# power-v3v8.net
KiCad netlist of a schematic drawn in Altium Designer
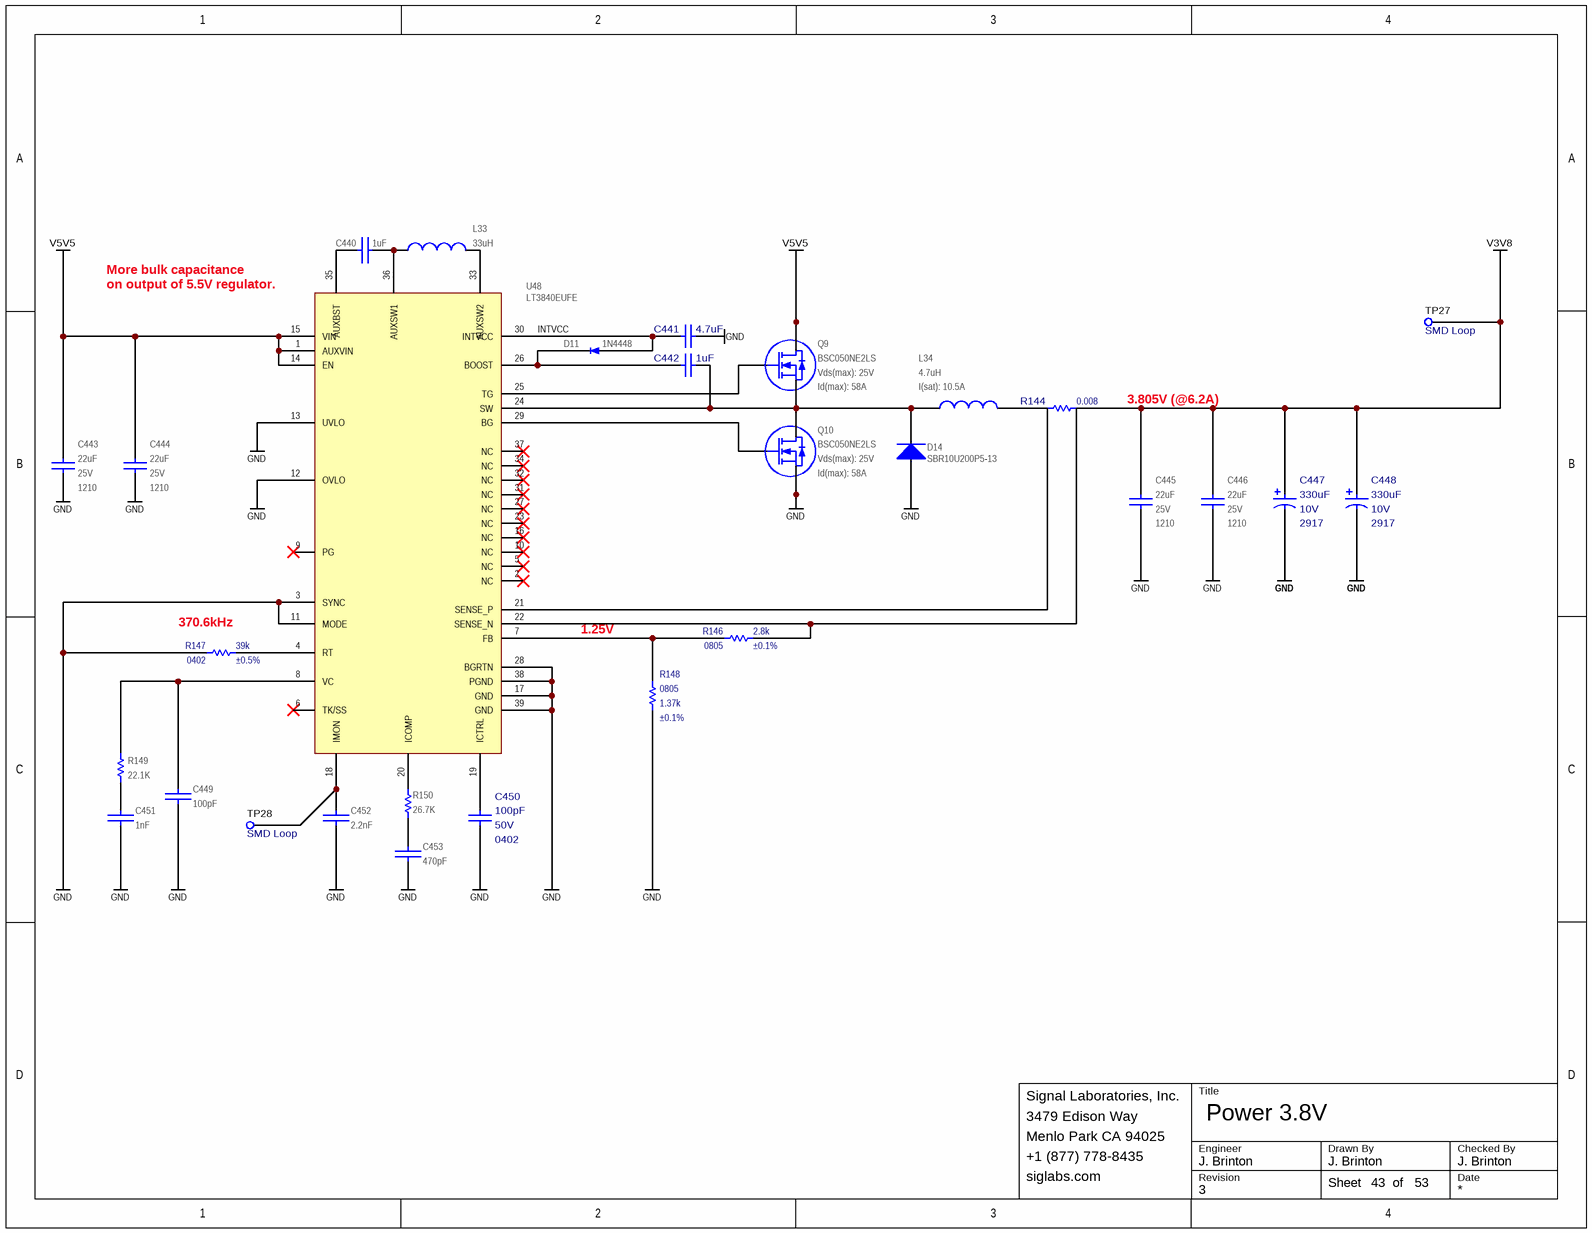
[diagram p0: power-v3v8.SchDoc]

(export (version "E")
  (design (tool "Eeschema 10.0.6"))
  (components
    (comp (ref "C440")
      (value "1uF")
      (footprint "CAPC100X50X55L25N")
      (description "Ceramic Capacitor 1uF ±10% 10V X5R 0402")
      (fields (field (name "MANUFACTURER") "Murata") (field (name "TOLERANCE") "±10%"))
      (libsource (lib "*") (part "CAP"))
    )
    (comp (ref "C441")
      (value "4.7uF")
      (footprint "CAPC160X80X90L20N")
      (description "Ceramic Capacitor 4.7uF ±10% 25V X5R 0603")
      (fields (field (name "MANUFACTURER") "Samsung") (field (name "TOLERANCE") "±10%"))
      (libsource (lib "capacitors") (part "CAP"))
    )
    (comp (ref "C442")
      (value "1uF")
      (footprint "CAPC100X50X55L25N")
      (description "Ceramic Capacitor 1uF ±10% 10V X5R 0402")
      (fields (field (name "MANUFACTURER") "Murata") (field (name "TOLERANCE") "±10%"))
      (libsource (lib "capacitors") (part "CAP"))
    )
    (comp (ref "C443")
      (value "22uF")
      (footprint "CAPC320X250X270L50N")
      (description "Ceramic Capacitor 22uF ±10% 25V X7R 1210")
      (fields
        (field (name "MANUFACTURER") "Murata")
        (field (name "TOLERANCE") "±10%")
        (field (name "VOLTAGE") "25V")
        (field (name "PACKAGE") "1210")
      )
      (libsource (lib "generic") (part "CAP"))
    )
    (comp (ref "C444")
      (value "22uF")
      (footprint "CAPC320X250X270L50N")
      (description "Ceramic Capacitor 22uF ±10% 25V X7R 1210")
      (fields
        (field (name "MANUFACTURER") "Murata")
        (field (name "TOLERANCE") "±10%")
        (field (name "VOLTAGE") "25V")
        (field (name "PACKAGE") "1210")
      )
      (libsource (lib "generic") (part "CAP"))
    )
    (comp (ref "C445")
      (value "22uF")
      (footprint "CAPC320X250X270L50N")
      (description "Ceramic Capacitor 22uF ±10% 25V X7R 1210")
      (fields
        (field (name "MANUFACTURER") "Murata")
        (field (name "TOLERANCE") "±10%")
        (field (name "VOLTAGE") "25V")
        (field (name "PACKAGE") "1210")
      )
      (libsource (lib "generic") (part "CAP"))
    )
    (comp (ref "C446")
      (value "22uF")
      (footprint "CAPC320X250X270L50N")
      (description "Ceramic Capacitor 22uF ±10% 25V X7R 1210")
      (fields
        (field (name "MANUFACTURER") "Murata")
        (field (name "TOLERANCE") "±10%")
        (field (name "VOLTAGE") "25V")
        (field (name "PACKAGE") "1210")
      )
      (libsource (lib "generic") (part "CAP"))
    )
    (comp (ref "C447")
      (value "330uF")
      (footprint "CAPPM730X435X310L135X240N")
      (description "Tantalum Capacitor 330uF ±10% 10V 2917")
      (fields
        (field (name "MANUFACTURER") "AVX")
        (field (name "TOLERANCE") "±10%")
        (field (name "PACKAGE") "2917")
        (field (name "VOLTAGE") "10V")
      )
      (libsource (lib "avx") (part "CAP_POL"))
    )
    (comp (ref "C448")
      (value "330uF")
      (footprint "CAPPM730X435X310L135X240N")
      (description "Tantalum Capacitor 330uF ±10% 10V 2917")
      (fields
        (field (name "MANUFACTURER") "AVX")
        (field (name "TOLERANCE") "±10%")
        (field (name "PACKAGE") "2917")
        (field (name "VOLTAGE") "10V")
      )
      (libsource (lib "avx") (part "CAP_POL"))
    )
    (comp (ref "C449")
      (value "100pF")
      (footprint "CAPC100X50X55L25N")
      (description "Ceramic Capacitor 100pF ±5% 50V NP0 0402")
      (fields (field (name "MANUFACTURER") "Murata") (field (name "VOLTAGE") "50V"))
      (libsource (lib "*") (part "CAP"))
    )
    (comp (ref "C450")
      (value "100pF")
      (footprint "generic:CAPC100X50X55L25N")
      (description "Ceramic Capacitor 100pF ±10% 50V C0G 0402")
      (fields
        (field (name "MANUFACTURER") "Vishay")
        (field (name "TOLERANCE") "±10%")
        (field (name "PACKAGE") "0402")
        (field (name "VOLTAGE") "50V")
      )
      (libsource (lib "capacitors") (part "CAP"))
    )
    (comp (ref "C451")
      (value "1nF")
      (footprint "CAPC100X50X55L25N")
      (description "Ceramic Capacitor 1nF ±5% 50V NP0 0402")
      (fields (field (name "MANUFACTURER") "Murata") (field (name "VOLTAGE") "50V"))
      (libsource (lib "*") (part "CAP"))
    )
    (comp (ref "C452")
      (value "2.2nF")
      (footprint "CAPC100X50X55L25N")
      (description "Ceramic Capacitor 2.2nF ±5% 25V NP0 0402")
      (fields (field (name "MANUFACTURER") "Kemet") (field (name "TOLERANCE") "±5%"))
      (libsource (lib "*") (part "CAP"))
    )
    (comp (ref "C453")
      (value "470pF")
      (footprint "CAPC100X50X55L25N")
      (description "Ceramic Capacitor 470pF ±5% 50V X7R 0402")
      (fields (field (name "MANUFACTURER") "Murata") (field (name "VOLTAGE") "50V"))
      (libsource (lib "*") (part "CAP"))
    )
    (comp (ref "D11")
      (value "1N4448HWS-7-F")
      (footprint "diodes_inc:SOD323")
      (description "Schottky Diode 80V 250mA SOD323")
      (fields (field (name "MANUFACTURER") "Diodes Inc") (field (name "ALTERNATIVE P/N") "1N4448"))
      (libsource (lib "diodes_inc") (part "1N4448HWS-7-F"))
    )
    (comp (ref "D14")
      (value "SBR10U200P5-13")
      (footprint "DIODES_POWERDI5")
      (description "Schottky Diode 200V 10A SMD")
      (fields (field (name "MANUFACTURER") "Diodes Inc"))
      (libsource (lib "diodes_inc") (part "PDS5100H"))
    )
    (comp (ref "L33")
      (value "33uH")
      (footprint "coilcraft:ME3220")
      (description "Inductor 33uH ±10% 500mA SMD")
      (fields (field (name "MANUFACTURER") "Coilcraft") (field (name "TOLERANCE") "±10%"))
      (libsource (lib "CamBoard_Pico_70.19K") (part "COIL"))
    )
    (comp (ref "L34")
      (value "4.7uH")
      (footprint "coilcraft:XAL6060")
      (description "Inductor 4.7uH,10.5A(sat), SMD")
      (fields
        (field (name "MANUFACTURER") "Coilcraft")
        (field (name "I(SAT)") "10.5A")
        (field (name "Comment") "XAL6060-472ME")
      )
      (libsource (lib "CamBoard_Pico_70.19K") (part "COIL"))
    )
    (comp (ref "Q9")
      (value "BSC050NE2LS")
      (footprint "TDSON-8")
      (description "MOSFET N-Channel Enhancement Mode")
      (fields
        (field (name "MANUFACTURER") "Infineon")
        (field (name "VDS(MAX)") "25V")
        (field (name "ID(MAX)") "58A")
      )
      (libsource (lib "infinion") (part "BSC190N15NS3"))
    )
    (comp (ref "Q10")
      (value "BSC050NE2LS")
      (footprint "TDSON-8")
      (description "MOSFET N-Channel Enhancement Mode")
      (fields
        (field (name "MANUFACTURER") "Infineon")
        (field (name "VDS(MAX)") "25V")
        (field (name "ID(MAX)") "58A")
      )
      (libsource (lib "infinion") (part "BSC190N15NS3"))
    )
    (comp (ref "R144")
      (value "0.008")
      (footprint "susumu:KRL3216T4")
      (description "Current Sense Resistor 8 mOhms +/-1% SMD 4-Terminal")
      (fields (field (name "TOLERANCE") "±1%") (field (name "MANUFACTURER") "Susumu"))
      (libsource (lib "susumu") (part "KRL3216T4A-M-R009-F"))
    )
    (comp (ref "R146")
      (value "2.8k")
      (footprint "RESC2012X70N")
      (description "Thin Film Resistor 2.8k +/-0.1% SMD 0805")
      (fields
        (field (name "TOLERANCE") "±0.1%")
        (field (name "MANUFACTURER") "Yageo")
        (field (name "PACKAGE") "0805")
        (field (name "Comment") "RT0805BRD072K8L")
      )
      (libsource (lib "generic") (part "RES"))
    )
    (comp (ref "R147")
      (value "39k")
      (footprint "RESC1005X40N")
      (description "Thin Film Resistor 39k +/-0.5% SMD 0402")
      (fields
        (field (name "TOLERANCE") "±0.5%")
        (field (name "MANUFACTURER") "Susumu")
        (field (name "PACKAGE") "0402")
        (field (name "Comment") "RR0510P-393-D")
      )
      (libsource (lib "generic") (part "RES"))
    )
    (comp (ref "R148")
      (value "1.37k")
      (footprint "RESC2012X70N")
      (description "Thin Film Resistor 1.37k +/-0.1% SMD 0805")
      (fields
        (field (name "TOLERANCE") "±0.1%")
        (field (name "MANUFACTURER") "Yageo")
        (field (name "PACKAGE") "0805")
        (field (name "Comment") "RT0805BRD071K37L")
      )
      (libsource (lib "generic") (part "RES"))
    )
    (comp (ref "R149")
      (value "22.1K")
      (footprint "generic:RESC1005X40N")
      (description "Thick Film Resistor 22.1k ±1% 0402")
      (fields (field (name "MANUFACTURER") "Panasonic") (field (name "TOLERANCE") "±1%"))
      (libsource (lib "Graviton") (part "RES 0402"))
    )
    (comp (ref "R150")
      (value "26.7K")
      (footprint "generic:RESC1005X40N")
      (description "Thick Film Resistor 26.7k ±1% 0402")
      (fields (field (name "MANUFACTURER") "Panasonic") (field (name "TOLERANCE") "±1%"))
      (libsource (lib "Graviton") (part "RES 0402"))
    )
    (comp (ref "TP27")
      (value "5015")
      (footprint "keystone:5015")
      (description "Test Point SMD")
      (fields (field (name "MANUFACTURER") "Keystone") (field (name "NOTES") "SMD Loop"))
      (libsource (lib "generic") (part "TEST_POINT_SMD_50"))
    )
    (comp (ref "TP28")
      (value "5015")
      (footprint "keystone:5015")
      (description "Test Point SMD")
      (fields (field (name "MANUFACTURER") "Keystone") (field (name "NOTES") "SMD Loop"))
      (libsource (lib "generic") (part "TEST_POINT_SMD_50"))
    )
    (comp (ref "U48")
      (value "LT3840EUFE")
      (footprint "linear:QFN39P40_600X400X80L40X20T465X265N")
      (description "Synchronous Regulator Controller")
      (fields (field (name "MANUFACTURER") "Linear Technology"))
      (libsource (lib "linear") (part "LT3840EUFE"))
    )
  )
  (nets
    (net (code "1") (name "/INTVCC") (class "Default")
      (node (ref "C441") (pin "1") (pinfunction "1_1") (pintype "passive"))
      (node (ref "D11") (pin "A") (pinfunction "A_A") (pintype "passive"))
      (node (ref "U48") (pin "30") (pinfunction "INTVCC_30") (pintype "passive"))
    )
    (net (code "2") (name "GND") (class "Default")
      (node (ref "C441") (pin "2") (pinfunction "2_2") (pintype "passive"))
      (node (ref "C443") (pin "1") (pinfunction "1_1") (pintype "passive"))
      (node (ref "C444") (pin "1") (pinfunction "1_1") (pintype "passive"))
      (node (ref "C445") (pin "1") (pinfunction "1_1") (pintype "passive"))
      (node (ref "C446") (pin "1") (pinfunction "1_1") (pintype "passive"))
      (node (ref "C447") (pin "2") (pinfunction "2_2") (pintype "passive"))
      (node (ref "C448") (pin "2") (pinfunction "2_2") (pintype "passive"))
      (node (ref "C449") (pin "1") (pinfunction "1_1") (pintype "passive"))
      (node (ref "C450") (pin "2") (pinfunction "2_2") (pintype "passive"))
      (node (ref "C451") (pin "2") (pinfunction "2_2") (pintype "passive"))
      (node (ref "C452") (pin "2") (pinfunction "2_2") (pintype "passive"))
      (node (ref "C453") (pin "1") (pinfunction "1_1") (pintype "passive"))
      (node (ref "D14") (pin "A") (pinfunction "A_A") (pintype "power_in"))
      (node (ref "Q10") (pin "1") (pinfunction "S_1") (pintype "passive"))
      (node (ref "Q10") (pin "2") (pinfunction "S_2") (pintype "passive"))
      (node (ref "Q10") (pin "3") (pinfunction "S_3") (pintype "passive"))
      (node (ref "R147") (pin "2") (pinfunction "2_2") (pintype "passive"))
      (node (ref "R148") (pin "1") (pinfunction "1_1") (pintype "passive"))
      (node (ref "U48") (pin "11") (pinfunction "MODE_11") (pintype "passive"))
      (node (ref "U48") (pin "12") (pinfunction "OVLO_12") (pintype "passive"))
      (node (ref "U48") (pin "13") (pinfunction "UVLO_13") (pintype "passive"))
      (node (ref "U48") (pin "17") (pinfunction "GND_17") (pintype "passive"))
      (node (ref "U48") (pin "28") (pinfunction "BGRTN_28") (pintype "passive"))
      (node (ref "U48") (pin "3") (pinfunction "SYNC_3") (pintype "passive"))
      (node (ref "U48") (pin "38") (pinfunction "PGND_38") (pintype "passive"))
      (node (ref "U48") (pin "39") (pinfunction "GND_39") (pintype "passive"))
    )
    (net (code "3") (name "Net-(C451-Pad1)") (class "Default")
      (node (ref "C451") (pin "1") (pinfunction "1_1") (pintype "passive"))
      (node (ref "R149") (pin "1") (pinfunction "1_1") (pintype "passive"))
    )
    (net (code "4") (name "Net-(C453-Pad2)") (class "Default")
      (node (ref "C453") (pin "2") (pinfunction "2_2") (pintype "passive"))
      (node (ref "R150") (pin "2") (pinfunction "2_2") (pintype "passive"))
    )
    (net (code "5") (name "Net-(L34-Pad2)") (class "Default")
      (node (ref "L34") (pin "2") (pinfunction "2_2") (pintype "passive"))
      (node (ref "R144") (pin "2") (pinfunction "2_2") (pintype "passive"))
    )
    (net (code "6") (name "Net-(Q9-G)") (class "Default")
      (node (ref "Q9") (pin "4") (pinfunction "G_4") (pintype "passive"))
      (node (ref "U48") (pin "25") (pinfunction "TG_25") (pintype "passive"))
    )
    (net (code "7") (name "Net-(Q10-G)") (class "Default")
      (node (ref "Q10") (pin "4") (pinfunction "G_4") (pintype "passive"))
      (node (ref "U48") (pin "29") (pinfunction "BG_29") (pintype "passive"))
    )
    (net (code "8") (name "Net-(U48-AUXBST)") (class "Default")
      (node (ref "C440") (pin "2") (pinfunction "2_2") (pintype "passive"))
      (node (ref "U48") (pin "35") (pinfunction "AUXBST_35") (pintype "passive"))
    )
    (net (code "9") (name "Net-(U48-AUXSW1)") (class "Default")
      (node (ref "C440") (pin "1") (pinfunction "1_1") (pintype "passive"))
      (node (ref "L33") (pin "1") (pinfunction "1_1") (pintype "passive"))
      (node (ref "U48") (pin "36") (pinfunction "AUXSW1_36") (pintype "passive"))
    )
    (net (code "10") (name "Net-(U48-AUXSW2)") (class "Default")
      (node (ref "L33") (pin "2") (pinfunction "2_2") (pintype "passive"))
      (node (ref "U48") (pin "33") (pinfunction "AUXSW2_33") (pintype "passive"))
    )
    (net (code "11") (name "Net-(U48-BOOST)") (class "Default")
      (node (ref "C442") (pin "1") (pinfunction "1_1") (pintype "passive"))
      (node (ref "D11") (pin "K") (pinfunction "K_K") (pintype "passive"))
      (node (ref "U48") (pin "26") (pinfunction "BOOST_26") (pintype "passive"))
    )
    (net (code "12") (name "Net-(U48-FB)") (class "Default")
      (node (ref "R146") (pin "2") (pinfunction "2_2") (pintype "passive"))
      (node (ref "R148") (pin "2") (pinfunction "2_2") (pintype "passive"))
      (node (ref "U48") (pin "7") (pinfunction "FB_7") (pintype "passive"))
    )
    (net (code "13") (name "Net-(U48-ICOMP)") (class "Default")
      (node (ref "R150") (pin "1") (pinfunction "1_1") (pintype "passive"))
      (node (ref "U48") (pin "20") (pinfunction "ICOMP_20") (pintype "passive"))
    )
    (net (code "14") (name "Net-(U48-ICTRL)") (class "Default")
      (node (ref "C450") (pin "1") (pinfunction "1_1") (pintype "passive"))
      (node (ref "U48") (pin "19") (pinfunction "ICTRL_19") (pintype "passive"))
    )
    (net (code "15") (name "Net-(U48-IMON)") (class "Default")
      (node (ref "C452") (pin "1") (pinfunction "1_1") (pintype "passive"))
      (node (ref "TP28") (pin "1") (pinfunction "1_1") (pintype "passive"))
      (node (ref "U48") (pin "18") (pinfunction "IMON_18") (pintype "passive"))
    )
    (net (code "16") (name "Net-(U48-RT)") (class "Default")
      (node (ref "R147") (pin "1") (pinfunction "1_1") (pintype "passive"))
      (node (ref "U48") (pin "4") (pinfunction "RT_4") (pintype "passive"))
    )
    (net (code "17") (name "Net-(U48-SENSE_N)") (class "Default")
      (node (ref "R144") (pin "3") (pinfunction "3_3") (pintype "passive"))
      (node (ref "R146") (pin "1") (pinfunction "1_1") (pintype "passive"))
      (node (ref "U48") (pin "22") (pinfunction "SENSE_N_22") (pintype "passive"))
    )
    (net (code "18") (name "Net-(U48-SENSE_P)") (class "Default")
      (node (ref "R144") (pin "4") (pinfunction "4_4") (pintype "passive"))
      (node (ref "U48") (pin "21") (pinfunction "SENSE_P_21") (pintype "passive"))
    )
    (net (code "19") (name "Net-(U48-SW)") (class "Default")
      (node (ref "C442") (pin "2") (pinfunction "2_2") (pintype "passive"))
      (node (ref "D14") (pin "K") (pinfunction "K_K") (pintype "passive"))
      (node (ref "L34") (pin "1") (pinfunction "1_1") (pintype "passive"))
      (node (ref "Q10") (pin "5") (pinfunction "D_5") (pintype "passive"))
      (node (ref "Q10") (pin "6") (pinfunction "D_6") (pintype "passive"))
      (node (ref "Q10") (pin "7") (pinfunction "D_7") (pintype "passive"))
      (node (ref "Q10") (pin "8") (pinfunction "D_8") (pintype "passive"))
      (node (ref "Q10") (pin "9") (pinfunction "D_9") (pintype "passive"))
      (node (ref "Q9") (pin "1") (pinfunction "S_1") (pintype "passive"))
      (node (ref "Q9") (pin "2") (pinfunction "S_2") (pintype "passive"))
      (node (ref "Q9") (pin "3") (pinfunction "S_3") (pintype "passive"))
      (node (ref "U48") (pin "24") (pinfunction "SW_24") (pintype "passive"))
    )
    (net (code "20") (name "Net-(U48-VC)") (class "Default")
      (node (ref "C449") (pin "2") (pinfunction "2_2") (pintype "passive"))
      (node (ref "R149") (pin "2") (pinfunction "2_2") (pintype "passive"))
      (node (ref "U48") (pin "8") (pinfunction "VC_8") (pintype "passive"))
    )
    (net (code "21") (name "V3V8") (class "Default")
      (node (ref "C445") (pin "2") (pinfunction "2_2") (pintype "passive"))
      (node (ref "C446") (pin "2") (pinfunction "2_2") (pintype "passive"))
      (node (ref "C447") (pin "1") (pinfunction "1_1") (pintype "passive"))
      (node (ref "C448") (pin "1") (pinfunction "1_1") (pintype "passive"))
      (node (ref "R144") (pin "1") (pinfunction "1_1") (pintype "passive"))
      (node (ref "TP27") (pin "1") (pinfunction "1_1") (pintype "passive"))
    )
    (net (code "22") (name "V5V5") (class "Default")
      (node (ref "C443") (pin "2") (pinfunction "2_2") (pintype "passive"))
      (node (ref "C444") (pin "2") (pinfunction "2_2") (pintype "passive"))
      (node (ref "Q9") (pin "5") (pinfunction "D_5") (pintype "passive"))
      (node (ref "Q9") (pin "6") (pinfunction "D_6") (pintype "passive"))
      (node (ref "Q9") (pin "7") (pinfunction "D_7") (pintype "passive"))
      (node (ref "Q9") (pin "8") (pinfunction "D_8") (pintype "passive"))
      (node (ref "Q9") (pin "9") (pinfunction "D_9") (pintype "passive"))
      (node (ref "U48") (pin "1") (pinfunction "AUXVIN_1") (pintype "passive"))
      (node (ref "U48") (pin "14") (pinfunction "EN_14") (pintype "passive"))
      (node (ref "U48") (pin "15") (pinfunction "VIN_15") (pintype "passive"))
    )
    (net (code "23") (name "unconnected-(U48-NC-Pad2)") (class "Default")
      (node (ref "U48") (pin "2") (pinfunction "NC_2") (pintype "passive+no_connect"))
    )
    (net (code "24") (name "unconnected-(U48-NC-Pad5)") (class "Default")
      (node (ref "U48") (pin "5") (pinfunction "NC_5") (pintype "passive+no_connect"))
    )
    (net (code "25") (name "unconnected-(U48-NC-Pad10)") (class "Default")
      (node (ref "U48") (pin "10") (pinfunction "NC_10") (pintype "passive+no_connect"))
    )
    (net (code "26") (name "unconnected-(U48-NC-Pad16)") (class "Default")
      (node (ref "U48") (pin "16") (pinfunction "NC_16") (pintype "passive+no_connect"))
    )
    (net (code "27") (name "unconnected-(U48-NC-Pad23)") (class "Default")
      (node (ref "U48") (pin "23") (pinfunction "NC_23") (pintype "passive+no_connect"))
    )
    (net (code "28") (name "unconnected-(U48-NC-Pad27)") (class "Default")
      (node (ref "U48") (pin "27") (pinfunction "NC_27") (pintype "passive+no_connect"))
    )
    (net (code "29") (name "unconnected-(U48-NC-Pad31)") (class "Default")
      (node (ref "U48") (pin "31") (pinfunction "NC_31") (pintype "passive+no_connect"))
    )
    (net (code "30") (name "unconnected-(U48-NC-Pad32)") (class "Default")
      (node (ref "U48") (pin "32") (pinfunction "NC_32") (pintype "passive+no_connect"))
    )
    (net (code "31") (name "unconnected-(U48-NC-Pad34)") (class "Default")
      (node (ref "U48") (pin "34") (pinfunction "NC_34") (pintype "passive+no_connect"))
    )
    (net (code "32") (name "unconnected-(U48-NC-Pad37)") (class "Default")
      (node (ref "U48") (pin "37") (pinfunction "NC_37") (pintype "passive+no_connect"))
    )
    (net (code "33") (name "unconnected-(U48-PG-Pad9)") (class "Default")
      (node (ref "U48") (pin "9") (pinfunction "PG_9") (pintype "passive+no_connect"))
    )
    (net (code "34") (name "unconnected-(U48-TK{slash}SS-Pad6)") (class "Default")
      (node (ref "U48") (pin "6") (pinfunction "TK/SS_6") (pintype "passive+no_connect"))
    )
  )
)
